# Cpcis_connectors_P4_P5_P6.net
KiCad netlist of a schematic drawn in Altium Designer
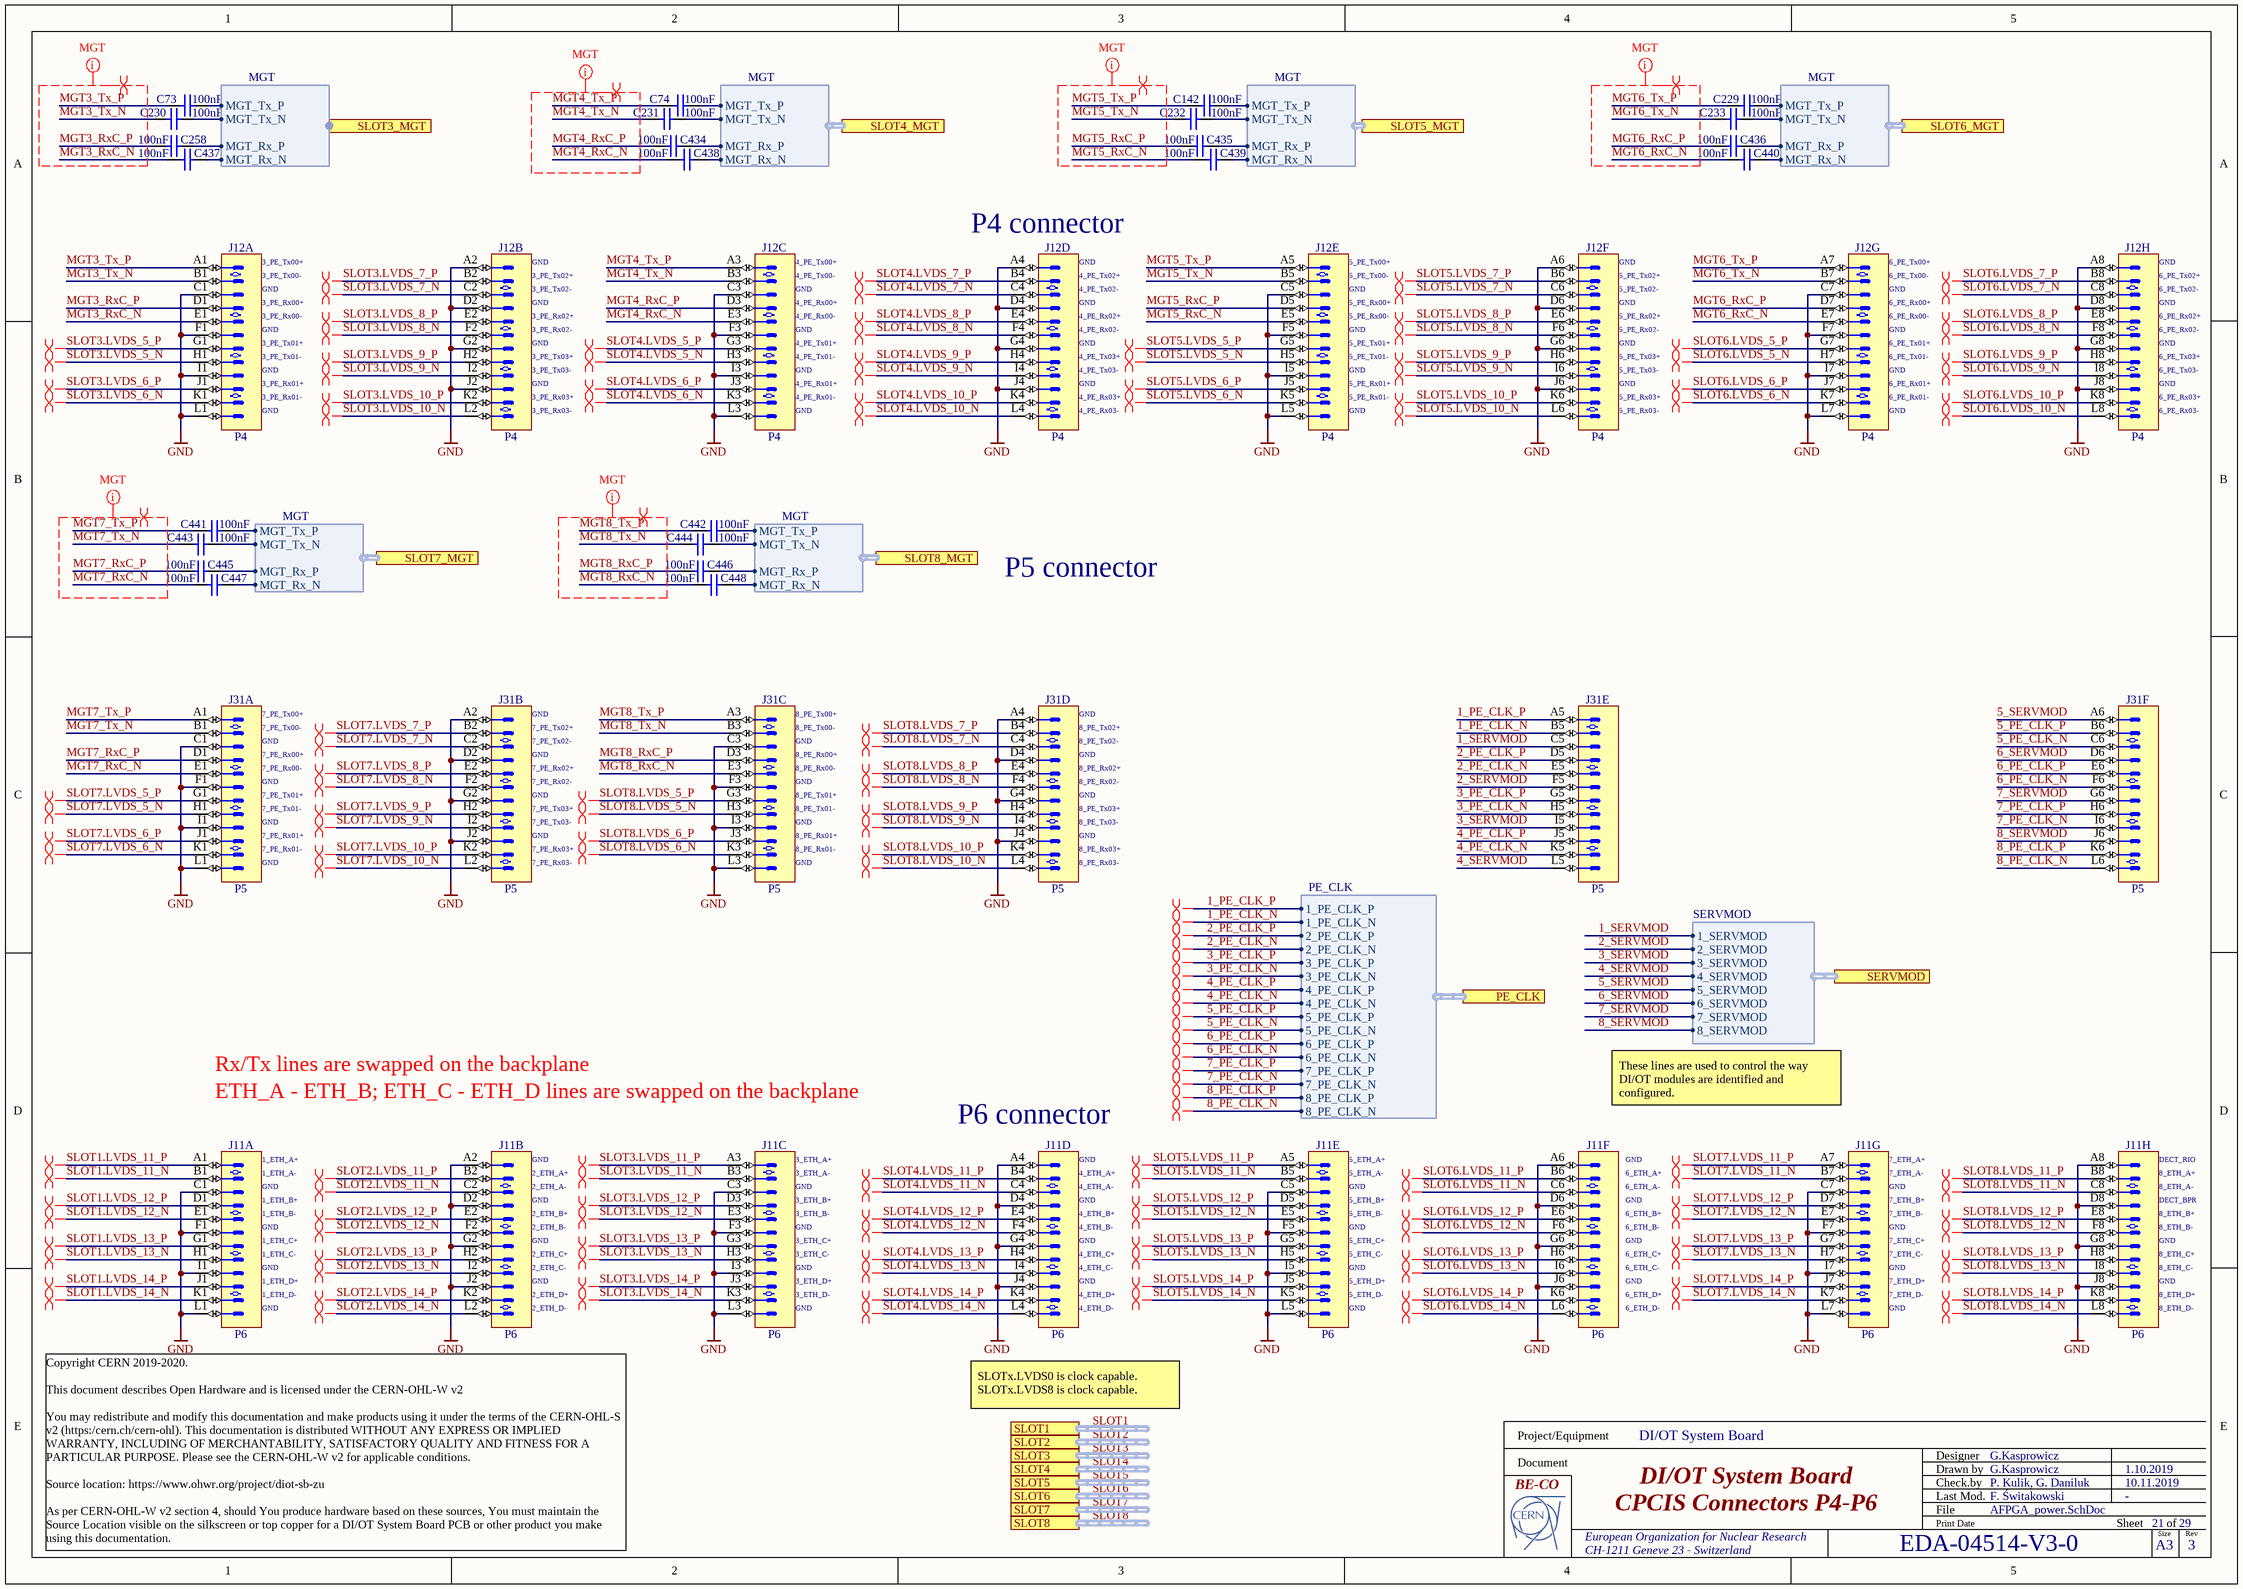
[diagram p0: Cpcis_connectors_P4_P5_P6.SchDoc]

(export (version "E")
  (design (tool "Eeschema 10.0.6"))
  (components
    (comp (ref "C73")
      (value "100nF")
      (footprint "CAPC0603X33N")
      (description "Non-polarised capacitor")
      (fields
        (field (name "PART NUMBER") "CC0201_100NF_6.3V_10%_X5R")
        (field (name "VOLTAGE") "6.3V")
        (field (name "AUTHOR") "CERN DEM JLC")
      )
      (libsource (lib "Capacitors") (part "Capacitor - non polarized"))
    )
    (comp (ref "C74")
      (value "100nF")
      (footprint "CAPC0603X33N")
      (description "Non-polarised capacitor")
      (fields
        (field (name "PART NUMBER") "CC0201_100NF_6.3V_10%_X5R")
        (field (name "VOLTAGE") "6.3V")
        (field (name "AUTHOR") "CERN DEM JLC")
      )
      (libsource (lib "Capacitors") (part "Capacitor - non polarized"))
    )
    (comp (ref "C142")
      (value "100nF")
      (footprint "CAPC0603X33N")
      (description "Non-polarised capacitor")
      (fields
        (field (name "PART NUMBER") "CC0201_100NF_6.3V_10%_X5R")
        (field (name "VOLTAGE") "6.3V")
        (field (name "AUTHOR") "CERN DEM JLC")
      )
      (libsource (lib "Capacitors") (part "Capacitor - non polarized"))
    )
    (comp (ref "C229")
      (value "100nF")
      (footprint "CAPC0603X33N")
      (description "Non-polarised capacitor")
      (fields
        (field (name "PART NUMBER") "CC0201_100NF_6.3V_10%_X5R")
        (field (name "VOLTAGE") "6.3V")
        (field (name "AUTHOR") "CERN DEM JLC")
      )
      (libsource (lib "Capacitors") (part "Capacitor - non polarized"))
    )
    (comp (ref "C230")
      (value "100nF")
      (footprint "CAPC0603X33N")
      (description "Non-polarised capacitor")
      (fields
        (field (name "PART NUMBER") "CC0201_100NF_6.3V_10%_X5R")
        (field (name "VOLTAGE") "6.3V")
        (field (name "AUTHOR") "CERN DEM JLC")
      )
      (libsource (lib "Capacitors") (part "Capacitor - non polarized"))
    )
    (comp (ref "C231")
      (value "100nF")
      (footprint "CAPC0603X33N")
      (description "Non-polarised capacitor")
      (fields
        (field (name "PART NUMBER") "CC0201_100NF_6.3V_10%_X5R")
        (field (name "VOLTAGE") "6.3V")
        (field (name "AUTHOR") "CERN DEM JLC")
      )
      (libsource (lib "Capacitors") (part "Capacitor - non polarized"))
    )
    (comp (ref "C232")
      (value "100nF")
      (footprint "CAPC0603X33N")
      (description "Non-polarised capacitor")
      (fields
        (field (name "PART NUMBER") "CC0201_100NF_6.3V_10%_X5R")
        (field (name "VOLTAGE") "6.3V")
        (field (name "AUTHOR") "CERN DEM JLC")
      )
      (libsource (lib "Capacitors") (part "Capacitor - non polarized"))
    )
    (comp (ref "C233")
      (value "100nF")
      (footprint "CAPC0603X33N")
      (description "Non-polarised capacitor")
      (fields
        (field (name "PART NUMBER") "CC0201_100NF_6.3V_10%_X5R")
        (field (name "VOLTAGE") "6.3V")
        (field (name "AUTHOR") "CERN DEM JLC")
      )
      (libsource (lib "Capacitors") (part "Capacitor - non polarized"))
    )
    (comp (ref "C258")
      (value "100nF")
      (footprint "CAPC0603X33N")
      (description "Non-polarised capacitor")
      (fields
        (field (name "PART NUMBER") "CC0201_100NF_6.3V_10%_X5R")
        (field (name "VOLTAGE") "6.3V")
        (field (name "AUTHOR") "CERN DEM JLC")
      )
      (libsource (lib "Capacitors") (part "Capacitor - non polarized"))
    )
    (comp (ref "C434")
      (value "100nF")
      (footprint "CAPC0603X33N")
      (description "Non-polarised capacitor")
      (fields
        (field (name "PART NUMBER") "CC0201_100NF_6.3V_10%_X5R")
        (field (name "VOLTAGE") "6.3V")
        (field (name "AUTHOR") "CERN DEM JLC")
      )
      (libsource (lib "Capacitors") (part "Capacitor - non polarized"))
    )
    (comp (ref "C435")
      (value "100nF")
      (footprint "CAPC0603X33N")
      (description "Non-polarised capacitor")
      (fields
        (field (name "PART NUMBER") "CC0201_100NF_6.3V_10%_X5R")
        (field (name "VOLTAGE") "6.3V")
        (field (name "AUTHOR") "CERN DEM JLC")
      )
      (libsource (lib "Capacitors") (part "Capacitor - non polarized"))
    )
    (comp (ref "C436")
      (value "100nF")
      (footprint "CAPC0603X33N")
      (description "Non-polarised capacitor")
      (fields
        (field (name "PART NUMBER") "CC0201_100NF_6.3V_10%_X5R")
        (field (name "VOLTAGE") "6.3V")
        (field (name "AUTHOR") "CERN DEM JLC")
      )
      (libsource (lib "Capacitors") (part "Capacitor - non polarized"))
    )
    (comp (ref "C437")
      (value "100nF")
      (footprint "CAPC0603X33N")
      (description "Non-polarised capacitor")
      (fields
        (field (name "PART NUMBER") "CC0201_100NF_6.3V_10%_X5R")
        (field (name "VOLTAGE") "6.3V")
        (field (name "AUTHOR") "CERN DEM JLC")
      )
      (libsource (lib "Capacitors") (part "Capacitor - non polarized"))
    )
    (comp (ref "C438")
      (value "100nF")
      (footprint "CAPC0603X33N")
      (description "Non-polarised capacitor")
      (fields
        (field (name "PART NUMBER") "CC0201_100NF_6.3V_10%_X5R")
        (field (name "VOLTAGE") "6.3V")
        (field (name "AUTHOR") "CERN DEM JLC")
      )
      (libsource (lib "Capacitors") (part "Capacitor - non polarized"))
    )
    (comp (ref "C439")
      (value "100nF")
      (footprint "CAPC0603X33N")
      (description "Non-polarised capacitor")
      (fields
        (field (name "PART NUMBER") "CC0201_100NF_6.3V_10%_X5R")
        (field (name "VOLTAGE") "6.3V")
        (field (name "AUTHOR") "CERN DEM JLC")
      )
      (libsource (lib "Capacitors") (part "Capacitor - non polarized"))
    )
    (comp (ref "C440")
      (value "100nF")
      (footprint "CAPC0603X33N")
      (description "Non-polarised capacitor")
      (fields
        (field (name "PART NUMBER") "CC0201_100NF_6.3V_10%_X5R")
        (field (name "VOLTAGE") "6.3V")
        (field (name "AUTHOR") "CERN DEM JLC")
      )
      (libsource (lib "Capacitors") (part "Capacitor - non polarized"))
    )
    (comp (ref "C441")
      (value "100nF")
      (footprint "CAPC0603X33N")
      (description "Non-polarised capacitor")
      (fields
        (field (name "PART NUMBER") "CC0201_100NF_6.3V_10%_X5R")
        (field (name "VOLTAGE") "6.3V")
        (field (name "AUTHOR") "CERN DEM JLC")
      )
      (libsource (lib "Capacitors") (part "Capacitor - non polarized"))
    )
    (comp (ref "C442")
      (value "100nF")
      (footprint "CAPC0603X33N")
      (description "Non-polarised capacitor")
      (fields
        (field (name "PART NUMBER") "CC0201_100NF_6.3V_10%_X5R")
        (field (name "VOLTAGE") "6.3V")
        (field (name "AUTHOR") "CERN DEM JLC")
      )
      (libsource (lib "Capacitors") (part "Capacitor - non polarized"))
    )
    (comp (ref "C443")
      (value "100nF")
      (footprint "CAPC0603X33N")
      (description "Non-polarised capacitor")
      (fields
        (field (name "PART NUMBER") "CC0201_100NF_6.3V_10%_X5R")
        (field (name "VOLTAGE") "6.3V")
        (field (name "AUTHOR") "CERN DEM JLC")
      )
      (libsource (lib "Capacitors") (part "Capacitor - non polarized"))
    )
    (comp (ref "C444")
      (value "100nF")
      (footprint "CAPC0603X33N")
      (description "Non-polarised capacitor")
      (fields
        (field (name "PART NUMBER") "CC0201_100NF_6.3V_10%_X5R")
        (field (name "VOLTAGE") "6.3V")
        (field (name "AUTHOR") "CERN DEM JLC")
      )
      (libsource (lib "Capacitors") (part "Capacitor - non polarized"))
    )
    (comp (ref "C445")
      (value "100nF")
      (footprint "CAPC0603X33N")
      (description "Non-polarised capacitor")
      (fields
        (field (name "PART NUMBER") "CC0201_100NF_6.3V_10%_X5R")
        (field (name "VOLTAGE") "6.3V")
        (field (name "AUTHOR") "CERN DEM JLC")
      )
      (libsource (lib "Capacitors") (part "Capacitor - non polarized"))
    )
    (comp (ref "C446")
      (value "100nF")
      (footprint "CAPC0603X33N")
      (description "Non-polarised capacitor")
      (fields
        (field (name "PART NUMBER") "CC0201_100NF_6.3V_10%_X5R")
        (field (name "VOLTAGE") "6.3V")
        (field (name "AUTHOR") "CERN DEM JLC")
      )
      (libsource (lib "Capacitors") (part "Capacitor - non polarized"))
    )
    (comp (ref "C447")
      (value "100nF")
      (footprint "CAPC0603X33N")
      (description "Non-polarised capacitor")
      (fields
        (field (name "PART NUMBER") "CC0201_100NF_6.3V_10%_X5R")
        (field (name "VOLTAGE") "6.3V")
        (field (name "AUTHOR") "CERN DEM JLC")
      )
      (libsource (lib "Capacitors") (part "Capacitor - non polarized"))
    )
    (comp (ref "C448")
      (value "100nF")
      (footprint "CAPC0603X33N")
      (description "Non-polarised capacitor")
      (fields
        (field (name "PART NUMBER") "CC0201_100NF_6.3V_10%_X5R")
        (field (name "VOLTAGE") "6.3V")
        (field (name "AUTHOR") "CERN DEM JLC")
      )
      (libsource (lib "Capacitors") (part "Capacitor - non polarized"))
    )
    (comp (ref "J11")
      (value "P6")
      (footprint "AMPHENOL_10052838-101LF")
      (description "96 Contacts Header, 8 Columns, 4 Pairs per Column")
      (fields
        (field (name "PART NUMBER") "AMPHENOL_10052838-101LF")
        (field (name "MANUFACTURER") "AMPHENOL")
        (field (name "AUTHOR") "CERN DEM MR")
      )
      (libsource (lib "Connectors") (part "AMPHENOL_10052838-101LF"))
    )
    (comp (ref "J12")
      (value "P4")
      (footprint "AMPHENOL_10052837-101LF")
      (description "96 Contacts Header, 8 Columns, 4 Pairs per Column")
      (fields
        (field (name "PART NUMBER") "AMPHENOL_10052837-101LF")
        (field (name "MANUFACTURER") "AMPHENOL")
        (field (name "AUTHOR") "CERN DEM MR")
      )
      (libsource (lib "Connectors") (part "AMPHENOL_10052837-101LF"))
    )
    (comp (ref "J31")
      (value "P5")
      (footprint "AMPHENOL_10052824-101LF")
      (description "72 Contacts Header, 6 Columns, 4 Pairs per Column")
      (fields
        (field (name "PART NUMBER") "AMPHENOL_10052824-101LF")
        (field (name "MANUFACTURER") "AMPHENOL")
        (field (name "AUTHOR") "CERN DEM JMW")
      )
      (libsource (lib "Connectors") (part "AMPHENOL_10052824-101LF"))
    )
  )
  (nets
    (net (code "12") (name "/1_PE_CLK_N") (class "Default")
      (node (ref "J31") (pin "B5") (pinfunction "B5_B5") (pintype "bidirectional"))
    )
    (net (code "13") (name "/1_PE_CLK_P") (class "Default")
      (node (ref "J31") (pin "A5") (pinfunction "A5_A5") (pintype "bidirectional"))
    )
    (net (code "14") (name "/1_SERVMOD") (class "Default")
      (node (ref "J31") (pin "C5") (pinfunction "C5_C5") (pintype "bidirectional"))
    )
    (net (code "15") (name "/2_PE_CLK_N") (class "Default")
      (node (ref "J31") (pin "E5") (pinfunction "E5_E5") (pintype "bidirectional"))
    )
    (net (code "16") (name "/2_PE_CLK_P") (class "Default")
      (node (ref "J31") (pin "D5") (pinfunction "D5_D5") (pintype "bidirectional"))
    )
    (net (code "17") (name "/2_SERVMOD") (class "Default")
      (node (ref "J31") (pin "F5") (pinfunction "F5_F5") (pintype "bidirectional"))
    )
    (net (code "18") (name "/3_PE_CLK_N") (class "Default")
      (node (ref "J31") (pin "H5") (pinfunction "H5_H5") (pintype "bidirectional"))
    )
    (net (code "19") (name "/3_PE_CLK_P") (class "Default")
      (node (ref "J31") (pin "G5") (pinfunction "G5_G5") (pintype "bidirectional"))
    )
    (net (code "20") (name "/3_SERVMOD") (class "Default")
      (node (ref "J31") (pin "I5") (pinfunction "I5_I5") (pintype "bidirectional"))
    )
    (net (code "21") (name "/4_PE_CLK_N") (class "Default")
      (node (ref "J31") (pin "K5") (pinfunction "K5_K5") (pintype "bidirectional"))
    )
    (net (code "22") (name "/4_PE_CLK_P") (class "Default")
      (node (ref "J31") (pin "J5") (pinfunction "J5_J5") (pintype "bidirectional"))
    )
    (net (code "23") (name "/4_SERVMOD") (class "Default")
      (node (ref "J31") (pin "L5") (pinfunction "L5_L5") (pintype "bidirectional"))
    )
    (net (code "24") (name "/5_PE_CLK_N") (class "Default")
      (node (ref "J31") (pin "C6") (pinfunction "C6_C6") (pintype "bidirectional"))
    )
    (net (code "25") (name "/5_PE_CLK_P") (class "Default")
      (node (ref "J31") (pin "B6") (pinfunction "B6_B6") (pintype "bidirectional"))
    )
    (net (code "26") (name "/5_SERVMOD") (class "Default")
      (node (ref "J31") (pin "A6") (pinfunction "A6_A6") (pintype "bidirectional"))
    )
    (net (code "27") (name "/6_PE_CLK_N") (class "Default")
      (node (ref "J31") (pin "F6") (pinfunction "F6_F6") (pintype "bidirectional"))
    )
    (net (code "28") (name "/6_PE_CLK_P") (class "Default")
      (node (ref "J31") (pin "E6") (pinfunction "E6_E6") (pintype "bidirectional"))
    )
    (net (code "29") (name "/6_SERVMOD") (class "Default")
      (node (ref "J31") (pin "D6") (pinfunction "D6_D6") (pintype "bidirectional"))
    )
    (net (code "30") (name "/7_PE_CLK_N") (class "Default")
      (node (ref "J31") (pin "I6") (pinfunction "I6_I6") (pintype "bidirectional"))
    )
    (net (code "31") (name "/7_PE_CLK_P") (class "Default")
      (node (ref "J31") (pin "H6") (pinfunction "H6_H6") (pintype "bidirectional"))
    )
    (net (code "32") (name "/7_SERVMOD") (class "Default")
      (node (ref "J31") (pin "G6") (pinfunction "G6_G6") (pintype "bidirectional"))
    )
    (net (code "33") (name "/8_PE_CLK_N") (class "Default")
      (node (ref "J31") (pin "L6") (pinfunction "L6_L6") (pintype "bidirectional"))
    )
    (net (code "34") (name "/8_PE_CLK_P") (class "Default")
      (node (ref "J31") (pin "K6") (pinfunction "K6_K6") (pintype "bidirectional"))
    )
    (net (code "35") (name "/8_SERVMOD") (class "Default")
      (node (ref "J31") (pin "J6") (pinfunction "J6_J6") (pintype "bidirectional"))
    )
    (net (code "36") (name "/MGT3_RxC_N") (class "Default")
      (node (ref "C437") (pin "1") (pinfunction "1_1") (pintype "passive"))
      (node (ref "J12") (pin "E1") (pinfunction "E1_E1") (pintype "bidirectional"))
    )
    (net (code "37") (name "/MGT3_RxC_P") (class "Default")
      (node (ref "C258") (pin "1") (pinfunction "1_1") (pintype "passive"))
      (node (ref "J12") (pin "D1") (pinfunction "D1_D1") (pintype "bidirectional"))
    )
    (net (code "38") (name "/MGT3_Tx_N") (class "Default")
      (node (ref "C230") (pin "2") (pinfunction "2_2") (pintype "passive"))
      (node (ref "J12") (pin "B1") (pinfunction "B1_B1") (pintype "bidirectional"))
    )
    (net (code "39") (name "/MGT3_Tx_P") (class "Default")
      (node (ref "C73") (pin "2") (pinfunction "2_2") (pintype "passive"))
      (node (ref "J12") (pin "A1") (pinfunction "A1_A1") (pintype "bidirectional"))
    )
    (net (code "40") (name "/MGT4_RxC_N") (class "Default")
      (node (ref "C438") (pin "1") (pinfunction "1_1") (pintype "passive"))
      (node (ref "J12") (pin "E3") (pinfunction "E3_E3") (pintype "bidirectional"))
    )
    (net (code "41") (name "/MGT4_RxC_P") (class "Default")
      (node (ref "C434") (pin "1") (pinfunction "1_1") (pintype "passive"))
      (node (ref "J12") (pin "D3") (pinfunction "D3_D3") (pintype "bidirectional"))
    )
    (net (code "42") (name "/MGT4_Tx_N") (class "Default")
      (node (ref "C231") (pin "2") (pinfunction "2_2") (pintype "passive"))
      (node (ref "J12") (pin "B3") (pinfunction "B3_B3") (pintype "bidirectional"))
    )
    (net (code "43") (name "/MGT4_Tx_P") (class "Default")
      (node (ref "C74") (pin "2") (pinfunction "2_2") (pintype "passive"))
      (node (ref "J12") (pin "A3") (pinfunction "A3_A3") (pintype "bidirectional"))
    )
    (net (code "44") (name "/MGT5_RxC_N") (class "Default")
      (node (ref "C439") (pin "1") (pinfunction "1_1") (pintype "passive"))
      (node (ref "J12") (pin "E5") (pinfunction "E5_E5") (pintype "bidirectional"))
    )
    (net (code "45") (name "/MGT5_RxC_P") (class "Default")
      (node (ref "C435") (pin "1") (pinfunction "1_1") (pintype "passive"))
      (node (ref "J12") (pin "D5") (pinfunction "D5_D5") (pintype "bidirectional"))
    )
    (net (code "46") (name "/MGT5_Tx_N") (class "Default")
      (node (ref "C232") (pin "2") (pinfunction "2_2") (pintype "passive"))
      (node (ref "J12") (pin "B5") (pinfunction "B5_B5") (pintype "bidirectional"))
    )
    (net (code "47") (name "/MGT5_Tx_P") (class "Default")
      (node (ref "C142") (pin "2") (pinfunction "2_2") (pintype "passive"))
      (node (ref "J12") (pin "A5") (pinfunction "A5_A5") (pintype "bidirectional"))
    )
    (net (code "48") (name "/MGT6_RxC_N") (class "Default")
      (node (ref "C440") (pin "1") (pinfunction "1_1") (pintype "passive"))
      (node (ref "J12") (pin "E7") (pinfunction "E7_E7") (pintype "bidirectional"))
    )
    (net (code "49") (name "/MGT6_RxC_P") (class "Default")
      (node (ref "C436") (pin "1") (pinfunction "1_1") (pintype "passive"))
      (node (ref "J12") (pin "D7") (pinfunction "D7_D7") (pintype "bidirectional"))
    )
    (net (code "50") (name "/MGT6_Tx_N") (class "Default")
      (node (ref "C233") (pin "2") (pinfunction "2_2") (pintype "passive"))
      (node (ref "J12") (pin "B7") (pinfunction "B7_B7") (pintype "bidirectional"))
    )
    (net (code "51") (name "/MGT6_Tx_P") (class "Default")
      (node (ref "C229") (pin "2") (pinfunction "2_2") (pintype "passive"))
      (node (ref "J12") (pin "A7") (pinfunction "A7_A7") (pintype "bidirectional"))
    )
    (net (code "52") (name "/MGT7_RxC_N") (class "Default")
      (node (ref "C447") (pin "1") (pinfunction "1_1") (pintype "passive"))
      (node (ref "J31") (pin "E1") (pinfunction "E1_E1") (pintype "bidirectional"))
    )
    (net (code "53") (name "/MGT7_RxC_P") (class "Default")
      (node (ref "C445") (pin "1") (pinfunction "1_1") (pintype "passive"))
      (node (ref "J31") (pin "D1") (pinfunction "D1_D1") (pintype "bidirectional"))
    )
    (net (code "54") (name "/MGT7_Tx_N") (class "Default")
      (node (ref "C443") (pin "2") (pinfunction "2_2") (pintype "passive"))
      (node (ref "J31") (pin "B1") (pinfunction "B1_B1") (pintype "bidirectional"))
    )
    (net (code "55") (name "/MGT7_Tx_P") (class "Default")
      (node (ref "C441") (pin "2") (pinfunction "2_2") (pintype "passive"))
      (node (ref "J31") (pin "A1") (pinfunction "A1_A1") (pintype "bidirectional"))
    )
    (net (code "56") (name "/MGT8_RxC_N") (class "Default")
      (node (ref "C448") (pin "1") (pinfunction "1_1") (pintype "passive"))
      (node (ref "J31") (pin "E3") (pinfunction "E3_E3") (pintype "bidirectional"))
    )
    (net (code "57") (name "/MGT8_RxC_P") (class "Default")
      (node (ref "C446") (pin "1") (pinfunction "1_1") (pintype "passive"))
      (node (ref "J31") (pin "D3") (pinfunction "D3_D3") (pintype "bidirectional"))
    )
    (net (code "58") (name "/MGT8_Tx_N") (class "Default")
      (node (ref "C444") (pin "2") (pinfunction "2_2") (pintype "passive"))
      (node (ref "J31") (pin "B3") (pinfunction "B3_B3") (pintype "bidirectional"))
    )
    (net (code "59") (name "/MGT8_Tx_P") (class "Default")
      (node (ref "C442") (pin "2") (pinfunction "2_2") (pintype "passive"))
      (node (ref "J31") (pin "A3") (pinfunction "A3_A3") (pintype "bidirectional"))
    )
    (net (code "60") (name "/SLOT1.LVDS_11_N") (class "Default")
      (node (ref "J11") (pin "B1") (pinfunction "B1_B1") (pintype "bidirectional"))
    )
    (net (code "61") (name "/SLOT1.LVDS_11_P") (class "Default")
      (node (ref "J11") (pin "A1") (pinfunction "A1_A1") (pintype "bidirectional"))
    )
    (net (code "62") (name "/SLOT1.LVDS_12_N") (class "Default")
      (node (ref "J11") (pin "E1") (pinfunction "E1_E1") (pintype "bidirectional"))
    )
    (net (code "63") (name "/SLOT1.LVDS_12_P") (class "Default")
      (node (ref "J11") (pin "D1") (pinfunction "D1_D1") (pintype "bidirectional"))
    )
    (net (code "64") (name "/SLOT1.LVDS_13_N") (class "Default")
      (node (ref "J11") (pin "H1") (pinfunction "H1_H1") (pintype "bidirectional"))
    )
    (net (code "65") (name "/SLOT1.LVDS_13_P") (class "Default")
      (node (ref "J11") (pin "G1") (pinfunction "G1_G1") (pintype "bidirectional"))
    )
    (net (code "66") (name "/SLOT1.LVDS_14_N") (class "Default")
      (node (ref "J11") (pin "K1") (pinfunction "K1_K1") (pintype "bidirectional"))
    )
    (net (code "67") (name "/SLOT1.LVDS_14_P") (class "Default")
      (node (ref "J11") (pin "J1") (pinfunction "J1_J1") (pintype "bidirectional"))
    )
    (net (code "68") (name "/SLOT2.LVDS_11_N") (class "Default")
      (node (ref "J11") (pin "C2") (pinfunction "C2_C2") (pintype "bidirectional"))
    )
    (net (code "69") (name "/SLOT2.LVDS_11_P") (class "Default")
      (node (ref "J11") (pin "B2") (pinfunction "B2_B2") (pintype "bidirectional"))
    )
    (net (code "70") (name "/SLOT2.LVDS_12_N") (class "Default")
      (node (ref "J11") (pin "F2") (pinfunction "F2_F2") (pintype "bidirectional"))
    )
    (net (code "71") (name "/SLOT2.LVDS_12_P") (class "Default")
      (node (ref "J11") (pin "E2") (pinfunction "E2_E2") (pintype "bidirectional"))
    )
    (net (code "72") (name "/SLOT2.LVDS_13_N") (class "Default")
      (node (ref "J11") (pin "I2") (pinfunction "I2_I2") (pintype "bidirectional"))
    )
    (net (code "73") (name "/SLOT2.LVDS_13_P") (class "Default")
      (node (ref "J11") (pin "H2") (pinfunction "H2_H2") (pintype "bidirectional"))
    )
    (net (code "74") (name "/SLOT2.LVDS_14_N") (class "Default")
      (node (ref "J11") (pin "L2") (pinfunction "L2_L2") (pintype "bidirectional"))
    )
    (net (code "75") (name "/SLOT2.LVDS_14_P") (class "Default")
      (node (ref "J11") (pin "K2") (pinfunction "K2_K2") (pintype "bidirectional"))
    )
    (net (code "76") (name "/SLOT3.LVDS_5_N") (class "Default")
      (node (ref "J12") (pin "H1") (pinfunction "H1_H1") (pintype "bidirectional"))
    )
    (net (code "77") (name "/SLOT3.LVDS_5_P") (class "Default")
      (node (ref "J12") (pin "G1") (pinfunction "G1_G1") (pintype "bidirectional"))
    )
    (net (code "78") (name "/SLOT3.LVDS_6_N") (class "Default")
      (node (ref "J12") (pin "K1") (pinfunction "K1_K1") (pintype "bidirectional"))
    )
    (net (code "79") (name "/SLOT3.LVDS_6_P") (class "Default")
      (node (ref "J12") (pin "J1") (pinfunction "J1_J1") (pintype "bidirectional"))
    )
    (net (code "80") (name "/SLOT3.LVDS_7_N") (class "Default")
      (node (ref "J12") (pin "C2") (pinfunction "C2_C2") (pintype "bidirectional"))
    )
    (net (code "81") (name "/SLOT3.LVDS_7_P") (class "Default")
      (node (ref "J12") (pin "B2") (pinfunction "B2_B2") (pintype "bidirectional"))
    )
    (net (code "82") (name "/SLOT3.LVDS_8_N") (class "Default")
      (node (ref "J12") (pin "F2") (pinfunction "F2_F2") (pintype "bidirectional"))
    )
    (net (code "83") (name "/SLOT3.LVDS_8_P") (class "Default")
      (node (ref "J12") (pin "E2") (pinfunction "E2_E2") (pintype "bidirectional"))
    )
    (net (code "84") (name "/SLOT3.LVDS_9_N") (class "Default")
      (node (ref "J12") (pin "I2") (pinfunction "I2_I2") (pintype "bidirectional"))
    )
    (net (code "85") (name "/SLOT3.LVDS_9_P") (class "Default")
      (node (ref "J12") (pin "H2") (pinfunction "H2_H2") (pintype "bidirectional"))
    )
    (net (code "86") (name "/SLOT3.LVDS_10_N") (class "Default")
      (node (ref "J12") (pin "L2") (pinfunction "L2_L2") (pintype "bidirectional"))
    )
    (net (code "87") (name "/SLOT3.LVDS_10_P") (class "Default")
      (node (ref "J12") (pin "K2") (pinfunction "K2_K2") (pintype "bidirectional"))
    )
    (net (code "88") (name "/SLOT3.LVDS_11_N") (class "Default")
      (node (ref "J11") (pin "B3") (pinfunction "B3_B3") (pintype "bidirectional"))
    )
    (net (code "89") (name "/SLOT3.LVDS_11_P") (class "Default")
      (node (ref "J11") (pin "A3") (pinfunction "A3_A3") (pintype "bidirectional"))
    )
    (net (code "90") (name "/SLOT3.LVDS_12_N") (class "Default")
      (node (ref "J11") (pin "E3") (pinfunction "E3_E3") (pintype "bidirectional"))
    )
    (net (code "91") (name "/SLOT3.LVDS_12_P") (class "Default")
      (node (ref "J11") (pin "D3") (pinfunction "D3_D3") (pintype "bidirectional"))
    )
    (net (code "92") (name "/SLOT3.LVDS_13_N") (class "Default")
      (node (ref "J11") (pin "H3") (pinfunction "H3_H3") (pintype "bidirectional"))
    )
    (net (code "93") (name "/SLOT3.LVDS_13_P") (class "Default")
      (node (ref "J11") (pin "G3") (pinfunction "G3_G3") (pintype "bidirectional"))
    )
    (net (code "94") (name "/SLOT3.LVDS_14_N") (class "Default")
      (node (ref "J11") (pin "K3") (pinfunction "K3_K3") (pintype "bidirectional"))
    )
    (net (code "95") (name "/SLOT3.LVDS_14_P") (class "Default")
      (node (ref "J11") (pin "J3") (pinfunction "J3_J3") (pintype "bidirectional"))
    )
    (net (code "96") (name "/SLOT4.LVDS_5_N") (class "Default")
      (node (ref "J12") (pin "H3") (pinfunction "H3_H3") (pintype "bidirectional"))
    )
    (net (code "97") (name "/SLOT4.LVDS_5_P") (class "Default")
      (node (ref "J12") (pin "G3") (pinfunction "G3_G3") (pintype "bidirectional"))
    )
    (net (code "98") (name "/SLOT4.LVDS_6_N") (class "Default")
      (node (ref "J12") (pin "K3") (pinfunction "K3_K3") (pintype "bidirectional"))
    )
    (net (code "99") (name "/SLOT4.LVDS_6_P") (class "Default")
      (node (ref "J12") (pin "J3") (pinfunction "J3_J3") (pintype "bidirectional"))
    )
    (net (code "100") (name "/SLOT4.LVDS_7_N") (class "Default")
      (node (ref "J12") (pin "C4") (pinfunction "C4_C4") (pintype "bidirectional"))
    )
    (net (code "101") (name "/SLOT4.LVDS_7_P") (class "Default")
      (node (ref "J12") (pin "B4") (pinfunction "B4_B4") (pintype "bidirectional"))
    )
    (net (code "102") (name "/SLOT4.LVDS_8_N") (class "Default")
      (node (ref "J12") (pin "F4") (pinfunction "F4_F4") (pintype "bidirectional"))
    )
    (net (code "103") (name "/SLOT4.LVDS_8_P") (class "Default")
      (node (ref "J12") (pin "E4") (pinfunction "E4_E4") (pintype "bidirectional"))
    )
    (net (code "104") (name "/SLOT4.LVDS_9_N") (class "Default")
      (node (ref "J12") (pin "I4") (pinfunction "I4_I4") (pintype "bidirectional"))
    )
    (net (code "105") (name "/SLOT4.LVDS_9_P") (class "Default")
      (node (ref "J12") (pin "H4") (pinfunction "H4_H4") (pintype "bidirectional"))
    )
    (net (code "106") (name "/SLOT4.LVDS_10_N") (class "Default")
      (node (ref "J12") (pin "L4") (pinfunction "L4_L4") (pintype "bidirectional"))
    )
    (net (code "107") (name "/SLOT4.LVDS_10_P") (class "Default")
      (node (ref "J12") (pin "K4") (pinfunction "K4_K4") (pintype "bidirectional"))
    )
    (net (code "108") (name "/SLOT4.LVDS_11_N") (class "Default")
      (node (ref "J11") (pin "C4") (pinfunction "C4_C4") (pintype "bidirectional"))
    )
    (net (code "109") (name "/SLOT4.LVDS_11_P") (class "Default")
      (node (ref "J11") (pin "B4") (pinfunction "B4_B4") (pintype "bidirectional"))
    )
    (net (code "110") (name "/SLOT4.LVDS_12_N") (class "Default")
      (node (ref "J11") (pin "F4") (pinfunction "F4_F4") (pintype "bidirectional"))
    )
    (net (code "111") (name "/SLOT4.LVDS_12_P") (class "Default")
      (node (ref "J11") (pin "E4") (pinfunction "E4_E4") (pintype "bidirectional"))
    )
    (net (code "112") (name "/SLOT4.LVDS_13_N") (class "Default")
      (node (ref "J11") (pin "I4") (pinfunction "I4_I4") (pintype "bidirectional"))
    )
    (net (code "113") (name "/SLOT4.LVDS_13_P") (class "Default")
      (node (ref "J11") (pin "H4") (pinfunction "H4_H4") (pintype "bidirectional"))
    )
    (net (code "114") (name "/SLOT4.LVDS_14_N") (class "Default")
      (node (ref "J11") (pin "L4") (pinfunction "L4_L4") (pintype "bidirectional"))
    )
    (net (code "115") (name "/SLOT4.LVDS_14_P") (class "Default")
      (node (ref "J11") (pin "K4") (pinfunction "K4_K4") (pintype "bidirectional"))
    )
    (net (code "116") (name "/SLOT5.LVDS_5_N") (class "Default")
      (node (ref "J12") (pin "H5") (pinfunction "H5_H5") (pintype "bidirectional"))
    )
    (net (code "117") (name "/SLOT5.LVDS_5_P") (class "Default")
      (node (ref "J12") (pin "G5") (pinfunction "G5_G5") (pintype "bidirectional"))
    )
    (net (code "118") (name "/SLOT5.LVDS_6_N") (class "Default")
      (node (ref "J12") (pin "K5") (pinfunction "K5_K5") (pintype "bidirectional"))
    )
    (net (code "119") (name "/SLOT5.LVDS_6_P") (class "Default")
      (node (ref "J12") (pin "J5") (pinfunction "J5_J5") (pintype "bidirectional"))
    )
    (net (code "120") (name "/SLOT5.LVDS_7_N") (class "Default")
      (node (ref "J12") (pin "C6") (pinfunction "C6_C6") (pintype "bidirectional"))
    )
    (net (code "121") (name "/SLOT5.LVDS_7_P") (class "Default")
      (node (ref "J12") (pin "B6") (pinfunction "B6_B6") (pintype "bidirectional"))
    )
    (net (code "122") (name "/SLOT5.LVDS_8_N") (class "Default")
      (node (ref "J12") (pin "F6") (pinfunction "F6_F6") (pintype "bidirectional"))
    )
    (net (code "123") (name "/SLOT5.LVDS_8_P") (class "Default")
      (node (ref "J12") (pin "E6") (pinfunction "E6_E6") (pintype "bidirectional"))
    )
    (net (code "124") (name "/SLOT5.LVDS_9_N") (class "Default")
      (node (ref "J12") (pin "I6") (pinfunction "I6_I6") (pintype "bidirectional"))
    )
    (net (code "125") (name "/SLOT5.LVDS_9_P") (class "Default")
      (node (ref "J12") (pin "H6") (pinfunction "H6_H6") (pintype "bidirectional"))
    )
    (net (code "126") (name "/SLOT5.LVDS_10_N") (class "Default")
      (node (ref "J12") (pin "L6") (pinfunction "L6_L6") (pintype "bidirectional"))
    )
    (net (code "127") (name "/SLOT5.LVDS_10_P") (class "Default")
      (node (ref "J12") (pin "K6") (pinfunction "K6_K6") (pintype "bidirectional"))
    )
    (net (code "128") (name "/SLOT5.LVDS_11_N") (class "Default")
      (node (ref "J11") (pin "B5") (pinfunction "B5_B5") (pintype "bidirectional"))
    )
    (net (code "129") (name "/SLOT5.LVDS_11_P") (class "Default")
      (node (ref "J11") (pin "A5") (pinfunction "A5_A5") (pintype "bidirectional"))
    )
    (net (code "130") (name "/SLOT5.LVDS_12_N") (class "Default")
      (node (ref "J11") (pin "E5") (pinfunction "E5_E5") (pintype "bidirectional"))
    )
    (net (code "131") (name "/SLOT5.LVDS_12_P") (class "Default")
      (node (ref "J11") (pin "D5") (pinfunction "D5_D5") (pintype "bidirectional"))
    )
    (net (code "132") (name "/SLOT5.LVDS_13_N") (class "Default")
      (node (ref "J11") (pin "H5") (pinfunction "H5_H5") (pintype "bidirectional"))
    )
    (net (code "133") (name "/SLOT5.LVDS_13_P") (class "Default")
      (node (ref "J11") (pin "G5") (pinfunction "G5_G5") (pintype "bidirectional"))
    )
    (net (code "134") (name "/SLOT5.LVDS_14_N") (class "Default")
      (node (ref "J11") (pin "K5") (pinfunction "K5_K5") (pintype "bidirectional"))
    )
    (net (code "135") (name "/SLOT5.LVDS_14_P") (class "Default")
      (node (ref "J11") (pin "J5") (pinfunction "J5_J5") (pintype "bidirectional"))
    )
    (net (code "136") (name "/SLOT6.LVDS_5_N") (class "Default")
      (node (ref "J12") (pin "H7") (pinfunction "H7_H7") (pintype "bidirectional"))
    )
    (net (code "137") (name "/SLOT6.LVDS_5_P") (class "Default")
      (node (ref "J12") (pin "G7") (pinfunction "G7_G7") (pintype "bidirectional"))
    )
    (net (code "138") (name "/SLOT6.LVDS_6_N") (class "Default")
      (node (ref "J12") (pin "K7") (pinfunction "K7_K7") (pintype "bidirectional"))
    )
    (net (code "139") (name "/SLOT6.LVDS_6_P") (class "Default")
      (node (ref "J12") (pin "J7") (pinfunction "J7_J7") (pintype "bidirectional"))
    )
    (net (code "140") (name "/SLOT6.LVDS_7_N") (class "Default")
      (node (ref "J12") (pin "C8") (pinfunction "C8_C8") (pintype "bidirectional"))
    )
    (net (code "141") (name "/SLOT6.LVDS_7_P") (class "Default")
      (node (ref "J12") (pin "B8") (pinfunction "B8_B8") (pintype "bidirectional"))
    )
    (net (code "142") (name "/SLOT6.LVDS_8_N") (class "Default")
      (node (ref "J12") (pin "F8") (pinfunction "F8_F8") (pintype "bidirectional"))
    )
    (net (code "143") (name "/SLOT6.LVDS_8_P") (class "Default")
      (node (ref "J12") (pin "E8") (pinfunction "E8_E8") (pintype "bidirectional"))
    )
    (net (code "144") (name "/SLOT6.LVDS_9_N") (class "Default")
      (node (ref "J12") (pin "I8") (pinfunction "I8_I8") (pintype "bidirectional"))
    )
    (net (code "145") (name "/SLOT6.LVDS_9_P") (class "Default")
      (node (ref "J12") (pin "H8") (pinfunction "H8_H8") (pintype "bidirectional"))
    )
    (net (code "146") (name "/SLOT6.LVDS_10_N") (class "Default")
      (node (ref "J12") (pin "L8") (pinfunction "L8_L8") (pintype "bidirectional"))
    )
    (net (code "147") (name "/SLOT6.LVDS_10_P") (class "Default")
      (node (ref "J12") (pin "K8") (pinfunction "K8_K8") (pintype "bidirectional"))
    )
    (net (code "148") (name "/SLOT6.LVDS_11_N") (class "Default")
      (node (ref "J11") (pin "C6") (pinfunction "C6_C6") (pintype "bidirectional"))
    )
    (net (code "149") (name "/SLOT6.LVDS_11_P") (class "Default")
      (node (ref "J11") (pin "B6") (pinfunction "B6_B6") (pintype "bidirectional"))
    )
    (net (code "150") (name "/SLOT6.LVDS_12_N") (class "Default")
      (node (ref "J11") (pin "F6") (pinfunction "F6_F6") (pintype "bidirectional"))
    )
    (net (code "151") (name "/SLOT6.LVDS_12_P") (class "Default")
      (node (ref "J11") (pin "E6") (pinfunction "E6_E6") (pintype "bidirectional"))
    )
    (net (code "152") (name "/SLOT6.LVDS_13_N") (class "Default")
      (node (ref "J11") (pin "I6") (pinfunction "I6_I6") (pintype "bidirectional"))
    )
    (net (code "153") (name "/SLOT6.LVDS_13_P") (class "Default")
      (node (ref "J11") (pin "H6") (pinfunction "H6_H6") (pintype "bidirectional"))
    )
    (net (code "154") (name "/SLOT6.LVDS_14_N") (class "Default")
      (node (ref "J11") (pin "L6") (pinfunction "L6_L6") (pintype "bidirectional"))
    )
    (net (code "155") (name "/SLOT6.LVDS_14_P") (class "Default")
      (node (ref "J11") (pin "K6") (pinfunction "K6_K6") (pintype "bidirectional"))
    )
    (net (code "156") (name "/SLOT7.LVDS_5_N") (class "Default")
      (node (ref "J31") (pin "H1") (pinfunction "H1_H1") (pintype "bidirectional"))
    )
    (net (code "157") (name "/SLOT7.LVDS_5_P") (class "Default")
      (node (ref "J31") (pin "G1") (pinfunction "G1_G1") (pintype "bidirectional"))
    )
    (net (code "158") (name "/SLOT7.LVDS_6_N") (class "Default")
      (node (ref "J31") (pin "K1") (pinfunction "K1_K1") (pintype "bidirectional"))
    )
    (net (code "159") (name "/SLOT7.LVDS_6_P") (class "Default")
      (node (ref "J31") (pin "J1") (pinfunction "J1_J1") (pintype "bidirectional"))
    )
    (net (code "160") (name "/SLOT7.LVDS_7_N") (class "Default")
      (node (ref "J31") (pin "C2") (pinfunction "C2_C2") (pintype "bidirectional"))
    )
    (net (code "161") (name "/SLOT7.LVDS_7_P") (class "Default")
      (node (ref "J31") (pin "B2") (pinfunction "B2_B2") (pintype "bidirectional"))
    )
    (net (code "162") (name "/SLOT7.LVDS_8_N") (class "Default")
      (node (ref "J31") (pin "F2") (pinfunction "F2_F2") (pintype "bidirectional"))
    )
    (net (code "163") (name "/SLOT7.LVDS_8_P") (class "Default")
      (node (ref "J31") (pin "E2") (pinfunction "E2_E2") (pintype "bidirectional"))
    )
    (net (code "164") (name "/SLOT7.LVDS_9_N") (class "Default")
      (node (ref "J31") (pin "I2") (pinfunction "I2_I2") (pintype "bidirectional"))
    )
    (net (code "165") (name "/SLOT7.LVDS_9_P") (class "Default")
      (node (ref "J31") (pin "H2") (pinfunction "H2_H2") (pintype "bidirectional"))
    )
    (net (code "166") (name "/SLOT7.LVDS_10_N") (class "Default")
      (node (ref "J31") (pin "L2") (pinfunction "L2_L2") (pintype "bidirectional"))
    )
    (net (code "167") (name "/SLOT7.LVDS_10_P") (class "Default")
      (node (ref "J31") (pin "K2") (pinfunction "K2_K2") (pintype "bidirectional"))
    )
    (net (code "168") (name "/SLOT7.LVDS_11_N") (class "Default")
      (node (ref "J11") (pin "B7") (pinfunction "B7_B7") (pintype "bidirectional"))
    )
    (net (code "169") (name "/SLOT7.LVDS_11_P") (class "Default")
      (node (ref "J11") (pin "A7") (pinfunction "A7_A7") (pintype "bidirectional"))
    )
    (net (code "170") (name "/SLOT7.LVDS_12_N") (class "Default")
      (node (ref "J11") (pin "E7") (pinfunction "E7_E7") (pintype "bidirectional"))
    )
    (net (code "171") (name "/SLOT7.LVDS_12_P") (class "Default")
      (node (ref "J11") (pin "D7") (pinfunction "D7_D7") (pintype "bidirectional"))
    )
    (net (code "172") (name "/SLOT7.LVDS_13_N") (class "Default")
      (node (ref "J11") (pin "H7") (pinfunction "H7_H7") (pintype "bidirectional"))
    )
    (net (code "173") (name "/SLOT7.LVDS_13_P") (class "Default")
      (node (ref "J11") (pin "G7") (pinfunction "G7_G7") (pintype "bidirectional"))
    )
    (net (code "174") (name "/SLOT7.LVDS_14_N") (class "Default")
      (node (ref "J11") (pin "K7") (pinfunction "K7_K7") (pintype "bidirectional"))
    )
    (net (code "175") (name "/SLOT7.LVDS_14_P") (class "Default")
      (node (ref "J11") (pin "J7") (pinfunction "J7_J7") (pintype "bidirectional"))
    )
    (net (code "176") (name "/SLOT8.LVDS_5_N") (class "Default")
      (node (ref "J31") (pin "H3") (pinfunction "H3_H3") (pintype "bidirectional"))
    )
    (net (code "177") (name "/SLOT8.LVDS_5_P") (class "Default")
      (node (ref "J31") (pin "G3") (pinfunction "G3_G3") (pintype "bidirectional"))
    )
    (net (code "178") (name "/SLOT8.LVDS_6_N") (class "Default")
      (node (ref "J31") (pin "K3") (pinfunction "K3_K3") (pintype "bidirectional"))
    )
    (net (code "179") (name "/SLOT8.LVDS_6_P") (class "Default")
      (node (ref "J31") (pin "J3") (pinfunction "J3_J3") (pintype "bidirectional"))
    )
    (net (code "180") (name "/SLOT8.LVDS_7_N") (class "Default")
      (node (ref "J31") (pin "C4") (pinfunction "C4_C4") (pintype "bidirectional"))
    )
    (net (code "181") (name "/SLOT8.LVDS_7_P") (class "Default")
      (node (ref "J31") (pin "B4") (pinfunction "B4_B4") (pintype "bidirectional"))
    )
    (net (code "182") (name "/SLOT8.LVDS_8_N") (class "Default")
      (node (ref "J31") (pin "F4") (pinfunction "F4_F4") (pintype "bidirectional"))
    )
    (net (code "183") (name "/SLOT8.LVDS_8_P") (class "Default")
      (node (ref "J31") (pin "E4") (pinfunction "E4_E4") (pintype "bidirectional"))
    )
    (net (code "184") (name "/SLOT8.LVDS_9_N") (class "Default")
      (node (ref "J31") (pin "I4") (pinfunction "I4_I4") (pintype "bidirectional"))
    )
    (net (code "185") (name "/SLOT8.LVDS_9_P") (class "Default")
      (node (ref "J31") (pin "H4") (pinfunction "H4_H4") (pintype "bidirectional"))
    )
    (net (code "186") (name "/SLOT8.LVDS_10_N") (class "Default")
      (node (ref "J31") (pin "L4") (pinfunction "L4_L4") (pintype "bidirectional"))
    )
    (net (code "187") (name "/SLOT8.LVDS_10_P") (class "Default")
      (node (ref "J31") (pin "K4") (pinfunction "K4_K4") (pintype "bidirectional"))
    )
    (net (code "188") (name "/SLOT8.LVDS_11_N") (class "Default")
      (node (ref "J11") (pin "C8") (pinfunction "C8_C8") (pintype "bidirectional"))
    )
    (net (code "189") (name "/SLOT8.LVDS_11_P") (class "Default")
      (node (ref "J11") (pin "B8") (pinfunction "B8_B8") (pintype "bidirectional"))
    )
    (net (code "190") (name "/SLOT8.LVDS_12_N") (class "Default")
      (node (ref "J11") (pin "F8") (pinfunction "F8_F8") (pintype "bidirectional"))
    )
    (net (code "191") (name "/SLOT8.LVDS_12_P") (class "Default")
      (node (ref "J11") (pin "E8") (pinfunction "E8_E8") (pintype "bidirectional"))
    )
    (net (code "192") (name "/SLOT8.LVDS_13_N") (class "Default")
      (node (ref "J11") (pin "I8") (pinfunction "I8_I8") (pintype "bidirectional"))
    )
    (net (code "193") (name "/SLOT8.LVDS_13_P") (class "Default")
      (node (ref "J11") (pin "H8") (pinfunction "H8_H8") (pintype "bidirectional"))
    )
    (net (code "194") (name "/SLOT8.LVDS_14_N") (class "Default")
      (node (ref "J11") (pin "L8") (pinfunction "L8_L8") (pintype "bidirectional"))
    )
    (net (code "195") (name "/SLOT8.LVDS_14_P") (class "Default")
      (node (ref "J11") (pin "K8") (pinfunction "K8_K8") (pintype "bidirectional"))
    )
    (net (code "207") (name "GND") (class "Default")
      (node (ref "J11") (pin "A2") (pinfunction "A2_A2") (pintype "bidirectional"))
      (node (ref "J11") (pin "A4") (pinfunction "A4_A4") (pintype "bidirectional"))
      (node (ref "J11") (pin "A6") (pinfunction "A6_A6") (pintype "bidirectional"))
      (node (ref "J11") (pin "A8") (pinfunction "A8_A8") (pintype "bidirectional"))
      (node (ref "J11") (pin "C1") (pinfunction "C1_C1") (pintype "bidirectional"))
      (node (ref "J11") (pin "C3") (pinfunction "C3_C3") (pintype "bidirectional"))
      (node (ref "J11") (pin "C5") (pinfunction "C5_C5") (pintype "bidirectional"))
      (node (ref "J11") (pin "C7") (pinfunction "C7_C7") (pintype "bidirectional"))
      (node (ref "J11") (pin "D2") (pinfunction "D2_D2") (pintype "bidirectional"))
      (node (ref "J11") (pin "D4") (pinfunction "D4_D4") (pintype "bidirectional"))
      (node (ref "J11") (pin "D6") (pinfunction "D6_D6") (pintype "bidirectional"))
      (node (ref "J11") (pin "D8") (pinfunction "D8_D8") (pintype "bidirectional"))
      (node (ref "J11") (pin "F1") (pinfunction "F1_F1") (pintype "bidirectional"))
      (node (ref "J11") (pin "F3") (pinfunction "F3_F3") (pintype "bidirectional"))
      (node (ref "J11") (pin "F5") (pinfunction "F5_F5") (pintype "bidirectional"))
      (node (ref "J11") (pin "F7") (pinfunction "F7_F7") (pintype "bidirectional"))
      (node (ref "J11") (pin "G2") (pinfunction "G2_G2") (pintype "bidirectional"))
      (node (ref "J11") (pin "G4") (pinfunction "G4_G4") (pintype "bidirectional"))
      (node (ref "J11") (pin "G6") (pinfunction "G6_G6") (pintype "bidirectional"))
      (node (ref "J11") (pin "G8") (pinfunction "G8_G8") (pintype "bidirectional"))
      (node (ref "J11") (pin "I1") (pinfunction "I1_I1") (pintype "bidirectional"))
      (node (ref "J11") (pin "I3") (pinfunction "I3_I3") (pintype "bidirectional"))
      (node (ref "J11") (pin "I5") (pinfunction "I5_I5") (pintype "bidirectional"))
      (node (ref "J11") (pin "I7") (pinfunction "I7_I7") (pintype "bidirectional"))
      (node (ref "J11") (pin "J2") (pinfunction "J2_J2") (pintype "bidirectional"))
      (node (ref "J11") (pin "J4") (pinfunction "J4_J4") (pintype "bidirectional"))
      (node (ref "J11") (pin "J6") (pinfunction "J6_J6") (pintype "bidirectional"))
      (node (ref "J11") (pin "J8") (pinfunction "J8_J8") (pintype "bidirectional"))
      (node (ref "J11") (pin "L1") (pinfunction "L1_L1") (pintype "bidirectional"))
      (node (ref "J11") (pin "L3") (pinfunction "L3_L3") (pintype "bidirectional"))
      (node (ref "J11") (pin "L5") (pinfunction "L5_L5") (pintype "bidirectional"))
      (node (ref "J11") (pin "L7") (pinfunction "L7_L7") (pintype "bidirectional"))
      (node (ref "J12") (pin "A2") (pinfunction "A2_A2") (pintype "bidirectional"))
      (node (ref "J12") (pin "A4") (pinfunction "A4_A4") (pintype "bidirectional"))
      (node (ref "J12") (pin "A6") (pinfunction "A6_A6") (pintype "bidirectional"))
      (node (ref "J12") (pin "A8") (pinfunction "A8_A8") (pintype "bidirectional"))
      (node (ref "J12") (pin "C1") (pinfunction "C1_C1") (pintype "bidirectional"))
      (node (ref "J12") (pin "C3") (pinfunction "C3_C3") (pintype "bidirectional"))
      (node (ref "J12") (pin "C5") (pinfunction "C5_C5") (pintype "bidirectional"))
      (node (ref "J12") (pin "C7") (pinfunction "C7_C7") (pintype "bidirectional"))
      (node (ref "J12") (pin "D2") (pinfunction "D2_D2") (pintype "bidirectional"))
      (node (ref "J12") (pin "D4") (pinfunction "D4_D4") (pintype "bidirectional"))
      (node (ref "J12") (pin "D6") (pinfunction "D6_D6") (pintype "bidirectional"))
      (node (ref "J12") (pin "D8") (pinfunction "D8_D8") (pintype "bidirectional"))
      (node (ref "J12") (pin "F1") (pinfunction "F1_F1") (pintype "bidirectional"))
      (node (ref "J12") (pin "F3") (pinfunction "F3_F3") (pintype "bidirectional"))
      (node (ref "J12") (pin "F5") (pinfunction "F5_F5") (pintype "bidirectional"))
      (node (ref "J12") (pin "F7") (pinfunction "F7_F7") (pintype "bidirectional"))
      (node (ref "J12") (pin "G2") (pinfunction "G2_G2") (pintype "bidirectional"))
      (node (ref "J12") (pin "G4") (pinfunction "G4_G4") (pintype "bidirectional"))
      (node (ref "J12") (pin "G6") (pinfunction "G6_G6") (pintype "bidirectional"))
      (node (ref "J12") (pin "G8") (pinfunction "G8_G8") (pintype "bidirectional"))
      (node (ref "J12") (pin "I1") (pinfunction "I1_I1") (pintype "bidirectional"))
      (node (ref "J12") (pin "I3") (pinfunction "I3_I3") (pintype "bidirectional"))
      (node (ref "J12") (pin "I5") (pinfunction "I5_I5") (pintype "bidirectional"))
      (node (ref "J12") (pin "I7") (pinfunction "I7_I7") (pintype "bidirectional"))
      (node (ref "J12") (pin "J2") (pinfunction "J2_J2") (pintype "bidirectional"))
      (node (ref "J12") (pin "J4") (pinfunction "J4_J4") (pintype "bidirectional"))
      (node (ref "J12") (pin "J6") (pinfunction "J6_J6") (pintype "bidirectional"))
      (node (ref "J12") (pin "J8") (pinfunction "J8_J8") (pintype "bidirectional"))
      (node (ref "J12") (pin "L1") (pinfunction "L1_L1") (pintype "bidirectional"))
      (node (ref "J12") (pin "L3") (pinfunction "L3_L3") (pintype "bidirectional"))
      (node (ref "J12") (pin "L5") (pinfunction "L5_L5") (pintype "bidirectional"))
      (node (ref "J12") (pin "L7") (pinfunction "L7_L7") (pintype "bidirectional"))
      (node (ref "J31") (pin "A2") (pinfunction "A2_A2") (pintype "bidirectional"))
      (node (ref "J31") (pin "A4") (pinfunction "A4_A4") (pintype "bidirectional"))
      (node (ref "J31") (pin "C1") (pinfunction "C1_C1") (pintype "bidirectional"))
      (node (ref "J31") (pin "C3") (pinfunction "C3_C3") (pintype "bidirectional"))
      (node (ref "J31") (pin "D2") (pinfunction "D2_D2") (pintype "bidirectional"))
      (node (ref "J31") (pin "D4") (pinfunction "D4_D4") (pintype "bidirectional"))
      (node (ref "J31") (pin "F1") (pinfunction "F1_F1") (pintype "bidirectional"))
      (node (ref "J31") (pin "F3") (pinfunction "F3_F3") (pintype "bidirectional"))
      (node (ref "J31") (pin "G2") (pinfunction "G2_G2") (pintype "bidirectional"))
      (node (ref "J31") (pin "G4") (pinfunction "G4_G4") (pintype "bidirectional"))
      (node (ref "J31") (pin "I1") (pinfunction "I1_I1") (pintype "bidirectional"))
      (node (ref "J31") (pin "I3") (pinfunction "I3_I3") (pintype "bidirectional"))
      (node (ref "J31") (pin "J2") (pinfunction "J2_J2") (pintype "bidirectional"))
      (node (ref "J31") (pin "J4") (pinfunction "J4_J4") (pintype "bidirectional"))
      (node (ref "J31") (pin "L1") (pinfunction "L1_L1") (pintype "bidirectional"))
      (node (ref "J31") (pin "L3") (pinfunction "L3_L3") (pintype "bidirectional"))
    )
    (net (code "208") (name "unconnected-(C73-Pad1)") (class "Default")
      (node (ref "C73") (pin "1") (pinfunction "1_1") (pintype "passive"))
    )
    (net (code "209") (name "unconnected-(C74-Pad1)") (class "Default")
      (node (ref "C74") (pin "1") (pinfunction "1_1") (pintype "passive"))
    )
    (net (code "210") (name "unconnected-(C142-Pad1)") (class "Default")
      (node (ref "C142") (pin "1") (pinfunction "1_1") (pintype "passive"))
    )
    (net (code "211") (name "unconnected-(C229-Pad1)") (class "Default")
      (node (ref "C229") (pin "1") (pinfunction "1_1") (pintype "passive"))
    )
    (net (code "212") (name "unconnected-(C230-Pad1)") (class "Default")
      (node (ref "C230") (pin "1") (pinfunction "1_1") (pintype "passive"))
    )
    (net (code "213") (name "unconnected-(C231-Pad1)") (class "Default")
      (node (ref "C231") (pin "1") (pinfunction "1_1") (pintype "passive"))
    )
    (net (code "214") (name "unconnected-(C232-Pad1)") (class "Default")
      (node (ref "C232") (pin "1") (pinfunction "1_1") (pintype "passive"))
    )
    (net (code "215") (name "unconnected-(C233-Pad1)") (class "Default")
      (node (ref "C233") (pin "1") (pinfunction "1_1") (pintype "passive"))
    )
    (net (code "216") (name "unconnected-(C258-Pad2)") (class "Default")
      (node (ref "C258") (pin "2") (pinfunction "2_2") (pintype "passive"))
    )
    (net (code "217") (name "unconnected-(C434-Pad2)") (class "Default")
      (node (ref "C434") (pin "2") (pinfunction "2_2") (pintype "passive"))
    )
    (net (code "218") (name "unconnected-(C435-Pad2)") (class "Default")
      (node (ref "C435") (pin "2") (pinfunction "2_2") (pintype "passive"))
    )
    (net (code "219") (name "unconnected-(C436-Pad2)") (class "Default")
      (node (ref "C436") (pin "2") (pinfunction "2_2") (pintype "passive"))
    )
    (net (code "220") (name "unconnected-(C437-Pad2)") (class "Default")
      (node (ref "C437") (pin "2") (pinfunction "2_2") (pintype "passive"))
    )
    (net (code "221") (name "unconnected-(C438-Pad2)") (class "Default")
      (node (ref "C438") (pin "2") (pinfunction "2_2") (pintype "passive"))
    )
    (net (code "222") (name "unconnected-(C439-Pad2)") (class "Default")
      (node (ref "C439") (pin "2") (pinfunction "2_2") (pintype "passive"))
    )
    (net (code "223") (name "unconnected-(C440-Pad2)") (class "Default")
      (node (ref "C440") (pin "2") (pinfunction "2_2") (pintype "passive"))
    )
    (net (code "224") (name "unconnected-(C441-Pad1)") (class "Default")
      (node (ref "C441") (pin "1") (pinfunction "1_1") (pintype "passive"))
    )
    (net (code "225") (name "unconnected-(C442-Pad1)") (class "Default")
      (node (ref "C442") (pin "1") (pinfunction "1_1") (pintype "passive"))
    )
    (net (code "226") (name "unconnected-(C443-Pad1)") (class "Default")
      (node (ref "C443") (pin "1") (pinfunction "1_1") (pintype "passive"))
    )
    (net (code "227") (name "unconnected-(C444-Pad1)") (class "Default")
      (node (ref "C444") (pin "1") (pinfunction "1_1") (pintype "passive"))
    )
    (net (code "228") (name "unconnected-(C445-Pad2)") (class "Default")
      (node (ref "C445") (pin "2") (pinfunction "2_2") (pintype "passive"))
    )
    (net (code "229") (name "unconnected-(C446-Pad2)") (class "Default")
      (node (ref "C446") (pin "2") (pinfunction "2_2") (pintype "passive"))
    )
    (net (code "230") (name "unconnected-(C447-Pad2)") (class "Default")
      (node (ref "C447") (pin "2") (pinfunction "2_2") (pintype "passive"))
    )
    (net (code "231") (name "unconnected-(C448-Pad2)") (class "Default")
      (node (ref "C448") (pin "2") (pinfunction "2_2") (pintype "passive"))
    )
  )
)
